# Schematic.net
KiCad netlist of a schematic drawn in Altium Designer
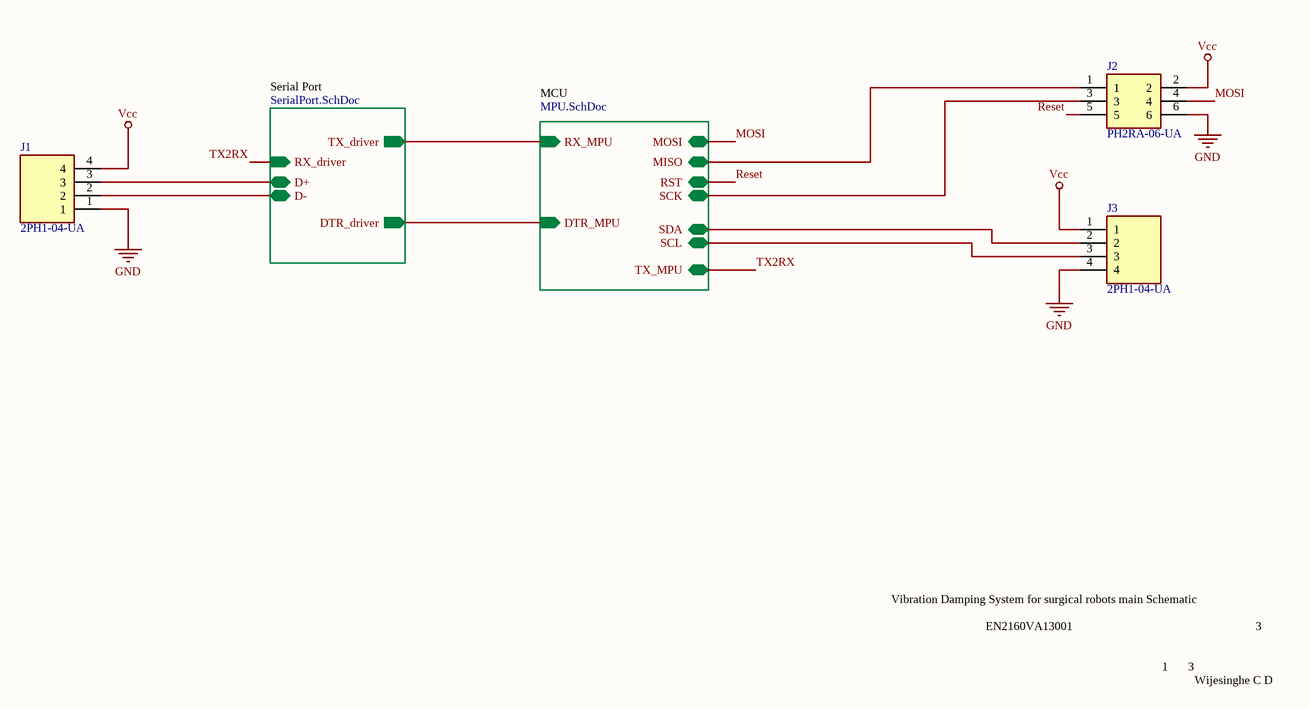
[diagram p0: Schematic.SchDoc]

(export (version "E")
  (design (tool "Eeschema 10.0.6"))
  (components
    (comp (ref "J1")
      (value "2PH1-04-UA")
      (footprint "SamacSys:HDRV4W50P0X200_1X4_800X200X590P")
      (description "Connector")
      (fields (field (name "MOUSER PART NUMBER") "737-2PH1-04-UA"))
      (libsource (lib "*") (part "2PH1-04-UA"))
    )
    (comp (ref "J2")
      (value "PH2RA-06-UA")
      (footprint "SamacSys:HDRRA6W64P254_2X3_762X250X500P")
      (description "Connector")
      (libsource (lib "*") (part "PH2RA-06-UA"))
    )
    (comp (ref "J3")
      (value "2PH1-04-UA")
      (footprint "SamacSys:HDRV4W50P0X200_1X4_800X200X590P")
      (description "Connector")
      (fields (field (name "MOUSER PART NUMBER") "737-2PH1-04-UA"))
      (libsource (lib "") (part "2PH1-04-UA_1"))
    )
  )
  (nets
    (net (code "1") (name "/D+") (class "Default")
      (node (ref "J1") (pin "3") (pinfunction "3_3") (pintype "passive"))
    )
    (net (code "2") (name "/D-") (class "Default")
      (node (ref "J1") (pin "2") (pinfunction "2_2") (pintype "passive"))
    )
    (net (code "4") (name "/MISO") (class "Default")
      (node (ref "J2") (pin "1") (pinfunction "1_1") (pintype "passive"))
    )
    (net (code "5") (name "/MOSI") (class "Default")
      (node (ref "J2") (pin "4") (pinfunction "4_4") (pintype "passive"))
    )
    (net (code "6") (name "/Reset") (class "Default")
      (node (ref "J2") (pin "5") (pinfunction "5_5") (pintype "passive"))
    )
    (net (code "7") (name "/SCK") (class "Default")
      (node (ref "J2") (pin "3") (pinfunction "3_3") (pintype "passive"))
    )
    (net (code "8") (name "/SCL") (class "Default")
      (node (ref "J3") (pin "3") (pinfunction "3_3") (pintype "passive"))
    )
    (net (code "9") (name "/SDA") (class "Default")
      (node (ref "J3") (pin "2") (pinfunction "2_2") (pintype "passive"))
    )
    (net (code "12") (name "GND") (class "Default")
      (node (ref "J1") (pin "1") (pinfunction "1_1") (pintype "passive"))
      (node (ref "J2") (pin "6") (pinfunction "6_6") (pintype "passive"))
      (node (ref "J3") (pin "4") (pinfunction "4_4") (pintype "passive"))
    )
    (net (code "13") (name "Vcc") (class "Default")
      (node (ref "J1") (pin "4") (pinfunction "4_4") (pintype "passive"))
      (node (ref "J2") (pin "2") (pinfunction "2_2") (pintype "passive"))
      (node (ref "J3") (pin "1") (pinfunction "1_1") (pintype "passive"))
    )
  )
)
